# Video_out.net
KiCad netlist of a schematic drawn in Altium Designer
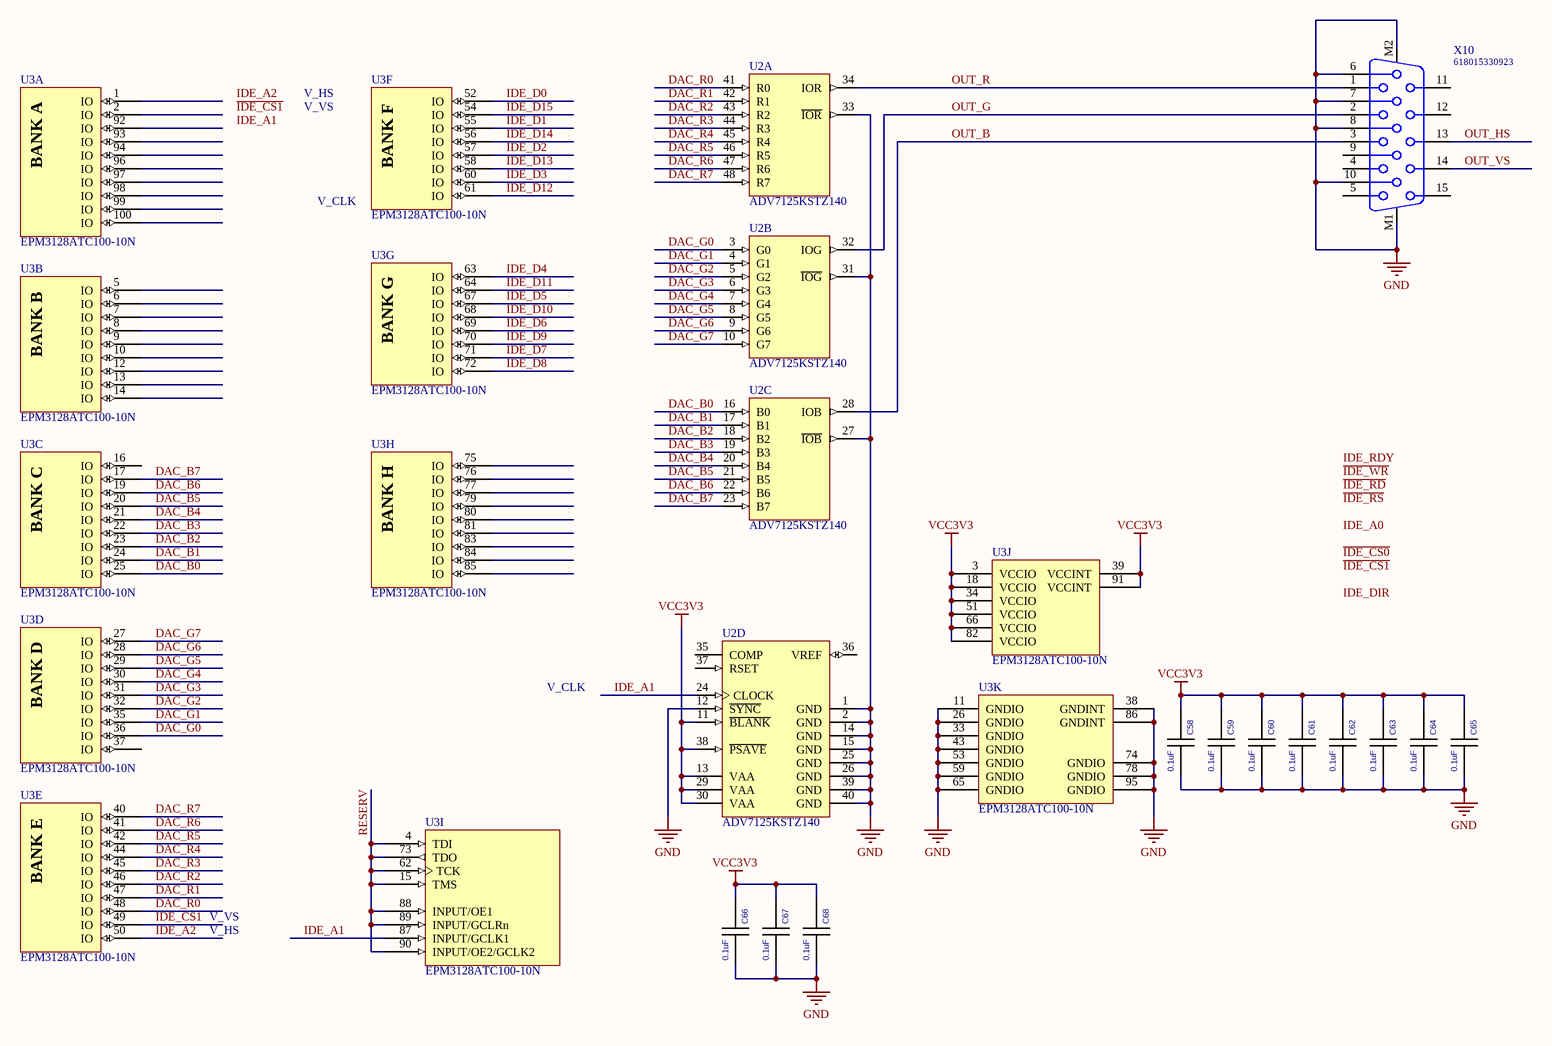
[diagram p0: Video out.SchDoc]

(export (version "E")
  (design (tool "Eeschema 10.0.6"))
  (components
    (comp (ref "C58")
      (value "0.1uF")
      (footprint "C-CHIP")
      (description "CAPCHIP")
      (libsource (lib "*") (part "CAPCHIP"))
    )
    (comp (ref "C59")
      (value "0.1uF")
      (footprint "C-CHIP")
      (description "CAPCHIP")
      (libsource (lib "*") (part "CAPCHIP"))
    )
    (comp (ref "C60")
      (value "0.1uF")
      (footprint "C-CHIP")
      (description "CAPCHIP")
      (libsource (lib "*") (part "CAPCHIP"))
    )
    (comp (ref "C61")
      (value "0.1uF")
      (footprint "C-CHIP")
      (description "CAPCHIP")
      (libsource (lib "*") (part "CAPCHIP"))
    )
    (comp (ref "C62")
      (value "0.1uF")
      (footprint "C-CHIP")
      (description "CAPCHIP")
      (libsource (lib "*") (part "CAPCHIP"))
    )
    (comp (ref "C63")
      (value "0.1uF")
      (footprint "C-CHIP")
      (description "CAPCHIP")
      (libsource (lib "*") (part "CAPCHIP"))
    )
    (comp (ref "C64")
      (value "0.1uF")
      (footprint "C-CHIP")
      (description "CAPCHIP")
      (libsource (lib "*") (part "CAPCHIP"))
    )
    (comp (ref "C65")
      (value "0.1uF")
      (footprint "C-CHIP")
      (description "CAPCHIP")
      (libsource (lib "*") (part "CAPCHIP"))
    )
    (comp (ref "C66")
      (value "0.1uF")
      (footprint "C-CHIP")
      (description "CAPCHIP")
      (libsource (lib "*") (part "CAPCHIP"))
    )
    (comp (ref "C67")
      (value "0.1uF")
      (footprint "C-CHIP")
      (description "CAPCHIP")
      (libsource (lib "*") (part "CAPCHIP"))
    )
    (comp (ref "C68")
      (value "0.1uF")
      (footprint "C-CHIP")
      (description "CAPCHIP")
      (libsource (lib "*") (part "CAPCHIP"))
    )
    (comp (ref "U2")
      (value "ADV7125KSTZ140")
      (footprint "ST-48_N")
      (fields (field (name "GENERIC PART NUMBER") "ADV7125") (field (name "MANUFACTURER") "Analog Devices"))
      (libsource (lib "Altium Content Vault") (part "ADI-ADV7125-ST-48"))
    )
    (comp (ref "U3")
      (value "EPM3128ATC100-10N")
      (footprint "ALTR-TQFP100_A-120_D1-140_L")
      (description "MAX(R) 3000A CPLD, 80 I/Os, Speed Grade 5, Commercial Grade, 100-Pin TQFP, RoHS")
      (fields (field (name "MANUFACTURER") "Altera"))
      (libsource (lib "Altium Content Vault") (part "ALTR-EPM3128A-TQFP-100"))
    )
    (comp (ref "X10")
      (value "618015330923")
      (footprint "618015330923")
      (description "Female High Density PCB Connector with Hex Screw WR-DSUB, Angled, 15 pins")
      (fields (field (name "MANUFACTURER") "Wurth Elektronik") (field (name "PUBLISHER") "WurthElektronik"))
      (libsource (lib "Altium Content Vault") (part "WE-CN-3S-2F-D15"))
    )
  )
  (nets
    (net (code "1") (name "/DAC_B0") (class "Default")
      (node (ref "U2") (pin "16") (pinfunction "B0_16") (pintype "input"))
      (node (ref "U3") (pin "25") (pinfunction "IO_25") (pintype "bidirectional"))
    )
    (net (code "2") (name "/DAC_B1") (class "Default")
      (node (ref "U2") (pin "17") (pinfunction "B1_17") (pintype "input"))
      (node (ref "U3") (pin "24") (pinfunction "IO_24") (pintype "bidirectional"))
    )
    (net (code "3") (name "/DAC_B2") (class "Default")
      (node (ref "U2") (pin "18") (pinfunction "B2_18") (pintype "input"))
      (node (ref "U3") (pin "23") (pinfunction "IO_23") (pintype "bidirectional"))
    )
    (net (code "4") (name "/DAC_B3") (class "Default")
      (node (ref "U2") (pin "19") (pinfunction "B3_19") (pintype "input"))
      (node (ref "U3") (pin "22") (pinfunction "IO_22") (pintype "bidirectional"))
    )
    (net (code "5") (name "/DAC_B4") (class "Default")
      (node (ref "U2") (pin "20") (pinfunction "B4_20") (pintype "input"))
      (node (ref "U3") (pin "21") (pinfunction "IO_21") (pintype "bidirectional"))
    )
    (net (code "6") (name "/DAC_B5") (class "Default")
      (node (ref "U2") (pin "21") (pinfunction "B5_21") (pintype "input"))
      (node (ref "U3") (pin "20") (pinfunction "IO_20") (pintype "bidirectional"))
    )
    (net (code "7") (name "/DAC_B6") (class "Default")
      (node (ref "U2") (pin "22") (pinfunction "B6_22") (pintype "input"))
      (node (ref "U3") (pin "19") (pinfunction "IO_19") (pintype "bidirectional"))
    )
    (net (code "8") (name "/DAC_B7") (class "Default")
      (node (ref "U2") (pin "23") (pinfunction "B7_23") (pintype "input"))
      (node (ref "U3") (pin "17") (pinfunction "IO_17") (pintype "bidirectional"))
    )
    (net (code "9") (name "/DAC_G0") (class "Default")
      (node (ref "U2") (pin "3") (pinfunction "G0_3") (pintype "input"))
      (node (ref "U3") (pin "36") (pinfunction "IO_36") (pintype "bidirectional"))
    )
    (net (code "10") (name "/DAC_G1") (class "Default")
      (node (ref "U2") (pin "4") (pinfunction "G1_4") (pintype "input"))
      (node (ref "U3") (pin "35") (pinfunction "IO_35") (pintype "bidirectional"))
    )
    (net (code "11") (name "/DAC_G2") (class "Default")
      (node (ref "U2") (pin "5") (pinfunction "G2_5") (pintype "input"))
      (node (ref "U3") (pin "32") (pinfunction "IO_32") (pintype "bidirectional"))
    )
    (net (code "12") (name "/DAC_G3") (class "Default")
      (node (ref "U2") (pin "6") (pinfunction "G3_6") (pintype "input"))
      (node (ref "U3") (pin "31") (pinfunction "IO_31") (pintype "bidirectional"))
    )
    (net (code "13") (name "/DAC_G4") (class "Default")
      (node (ref "U2") (pin "7") (pinfunction "G4_7") (pintype "input"))
      (node (ref "U3") (pin "30") (pinfunction "IO_30") (pintype "bidirectional"))
    )
    (net (code "14") (name "/DAC_G5") (class "Default")
      (node (ref "U2") (pin "8") (pinfunction "G5_8") (pintype "input"))
      (node (ref "U3") (pin "29") (pinfunction "IO_29") (pintype "bidirectional"))
    )
    (net (code "15") (name "/DAC_G6") (class "Default")
      (node (ref "U2") (pin "9") (pinfunction "G6_9") (pintype "input"))
      (node (ref "U3") (pin "28") (pinfunction "IO_28") (pintype "bidirectional"))
    )
    (net (code "16") (name "/DAC_G7") (class "Default")
      (node (ref "U2") (pin "10") (pinfunction "G7_10") (pintype "input"))
      (node (ref "U3") (pin "27") (pinfunction "IO_27") (pintype "bidirectional"))
    )
    (net (code "17") (name "/DAC_R0") (class "Default")
      (node (ref "U2") (pin "41") (pinfunction "R0_41") (pintype "input"))
      (node (ref "U3") (pin "48") (pinfunction "IO_48") (pintype "bidirectional"))
    )
    (net (code "18") (name "/DAC_R1") (class "Default")
      (node (ref "U2") (pin "42") (pinfunction "R1_42") (pintype "input"))
      (node (ref "U3") (pin "47") (pinfunction "IO_47") (pintype "bidirectional"))
    )
    (net (code "19") (name "/DAC_R2") (class "Default")
      (node (ref "U2") (pin "43") (pinfunction "R2_43") (pintype "input"))
      (node (ref "U3") (pin "46") (pinfunction "IO_46") (pintype "bidirectional"))
    )
    (net (code "20") (name "/DAC_R3") (class "Default")
      (node (ref "U2") (pin "44") (pinfunction "R3_44") (pintype "input"))
      (node (ref "U3") (pin "45") (pinfunction "IO_45") (pintype "bidirectional"))
    )
    (net (code "21") (name "/DAC_R4") (class "Default")
      (node (ref "U2") (pin "45") (pinfunction "R4_45") (pintype "input"))
      (node (ref "U3") (pin "44") (pinfunction "IO_44") (pintype "bidirectional"))
    )
    (net (code "22") (name "/DAC_R5") (class "Default")
      (node (ref "U2") (pin "46") (pinfunction "R5_46") (pintype "input"))
      (node (ref "U3") (pin "42") (pinfunction "IO_42") (pintype "bidirectional"))
    )
    (net (code "23") (name "/DAC_R6") (class "Default")
      (node (ref "U2") (pin "47") (pinfunction "R6_47") (pintype "input"))
      (node (ref "U3") (pin "41") (pinfunction "IO_41") (pintype "bidirectional"))
    )
    (net (code "24") (name "/DAC_R7") (class "Default")
      (node (ref "U2") (pin "48") (pinfunction "R7_48") (pintype "input"))
      (node (ref "U3") (pin "40") (pinfunction "IO_40") (pintype "bidirectional"))
    )
    (net (code "26") (name "/IDE_A1") (class "Default")
      (node (ref "U2") (pin "24") (pinfunction "CLOCK_24") (pintype "input"))
      (node (ref "U3") (pin "87") (pinfunction "INPUT/GCLK1_87") (pintype "input"))
    )
    (net (code "27") (name "/IDE_A2") (class "Default")
      (node (ref "U3") (pin "50") (pinfunction "IO_50") (pintype "bidirectional"))
    )
    (net (code "28") (name "/IDE_D0") (class "Default")
      (node (ref "U3") (pin "52") (pinfunction "IO_52") (pintype "bidirectional"))
    )
    (net (code "29") (name "/IDE_D1") (class "Default")
      (node (ref "U3") (pin "55") (pinfunction "IO_55") (pintype "bidirectional"))
    )
    (net (code "30") (name "/IDE_D2") (class "Default")
      (node (ref "U3") (pin "57") (pinfunction "IO_57") (pintype "bidirectional"))
    )
    (net (code "31") (name "/IDE_D3") (class "Default")
      (node (ref "U3") (pin "60") (pinfunction "IO_60") (pintype "bidirectional"))
    )
    (net (code "32") (name "/IDE_D4") (class "Default")
      (node (ref "U3") (pin "63") (pinfunction "IO_63") (pintype "bidirectional"))
    )
    (net (code "33") (name "/IDE_D5") (class "Default")
      (node (ref "U3") (pin "67") (pinfunction "IO_67") (pintype "bidirectional"))
    )
    (net (code "34") (name "/IDE_D6") (class "Default")
      (node (ref "U3") (pin "69") (pinfunction "IO_69") (pintype "bidirectional"))
    )
    (net (code "35") (name "/IDE_D7") (class "Default")
      (node (ref "U3") (pin "71") (pinfunction "IO_71") (pintype "bidirectional"))
    )
    (net (code "36") (name "/IDE_D8") (class "Default")
      (node (ref "U3") (pin "72") (pinfunction "IO_72") (pintype "bidirectional"))
    )
    (net (code "37") (name "/IDE_D9") (class "Default")
      (node (ref "U3") (pin "70") (pinfunction "IO_70") (pintype "bidirectional"))
    )
    (net (code "38") (name "/IDE_D10") (class "Default")
      (node (ref "U3") (pin "68") (pinfunction "IO_68") (pintype "bidirectional"))
    )
    (net (code "39") (name "/IDE_D11") (class "Default")
      (node (ref "U3") (pin "64") (pinfunction "IO_64") (pintype "bidirectional"))
    )
    (net (code "40") (name "/IDE_D12") (class "Default")
      (node (ref "U3") (pin "61") (pinfunction "IO_61") (pintype "bidirectional"))
    )
    (net (code "41") (name "/IDE_D13") (class "Default")
      (node (ref "U3") (pin "58") (pinfunction "IO_58") (pintype "bidirectional"))
    )
    (net (code "42") (name "/IDE_D14") (class "Default")
      (node (ref "U3") (pin "56") (pinfunction "IO_56") (pintype "bidirectional"))
    )
    (net (code "43") (name "/IDE_D15") (class "Default")
      (node (ref "U3") (pin "54") (pinfunction "IO_54") (pintype "bidirectional"))
    )
    (net (code "46") (name "/OUT_B") (class "Default")
      (node (ref "U2") (pin "28") (pinfunction "IOB_28") (pintype "output"))
      (node (ref "X10") (pin "3") (pinfunction "3_3") (pintype "passive"))
    )
    (net (code "47") (name "/OUT_G") (class "Default")
      (node (ref "U2") (pin "32") (pinfunction "IOG_32") (pintype "output"))
      (node (ref "X10") (pin "2") (pinfunction "2_2") (pintype "passive"))
    )
    (net (code "48") (name "/OUT_HS") (class "Default")
      (node (ref "X10") (pin "13") (pinfunction "13_13") (pintype "passive"))
    )
    (net (code "49") (name "/OUT_R") (class "Default")
      (node (ref "U2") (pin "34") (pinfunction "IOR_34") (pintype "output"))
      (node (ref "X10") (pin "1") (pinfunction "1_1") (pintype "passive"))
    )
    (net (code "50") (name "/OUT_VS") (class "Default")
      (node (ref "X10") (pin "14") (pinfunction "14_14") (pintype "passive"))
    )
    (net (code "51") (name "/RESERV") (class "Default")
      (node (ref "U3") (pin "15") (pinfunction "TMS_15") (pintype "input"))
      (node (ref "U3") (pin "4") (pinfunction "TDI_4") (pintype "input"))
      (node (ref "U3") (pin "62") (pinfunction "TCK_62") (pintype "input"))
      (node (ref "U3") (pin "73") (pinfunction "TDO_73") (pintype "output"))
      (node (ref "U3") (pin "88") (pinfunction "INPUT/OE1_88") (pintype "input"))
      (node (ref "U3") (pin "89") (pinfunction "INPUT/GCLRn_89") (pintype "input"))
      (node (ref "U3") (pin "90") (pinfunction "INPUT/OE2/GCLK2_90") (pintype "input"))
    )
    (net (code "53") (name "/~{IDE_CS1}") (class "Default")
      (node (ref "U3") (pin "49") (pinfunction "IO_49") (pintype "bidirectional"))
    )
    (net (code "57") (name "GND") (class "Default")
      (node (ref "C58") (pin "2") (pinfunction "2_2") (pintype "passive"))
      (node (ref "C59") (pin "2") (pinfunction "2_2") (pintype "passive"))
      (node (ref "C60") (pin "2") (pinfunction "2_2") (pintype "passive"))
      (node (ref "C61") (pin "2") (pinfunction "2_2") (pintype "passive"))
      (node (ref "C62") (pin "2") (pinfunction "2_2") (pintype "passive"))
      (node (ref "C63") (pin "2") (pinfunction "2_2") (pintype "passive"))
      (node (ref "C64") (pin "2") (pinfunction "2_2") (pintype "passive"))
      (node (ref "C65") (pin "2") (pinfunction "2_2") (pintype "passive"))
      (node (ref "C66") (pin "2") (pinfunction "2_2") (pintype "passive"))
      (node (ref "C67") (pin "2") (pinfunction "2_2") (pintype "passive"))
      (node (ref "C68") (pin "2") (pinfunction "2_2") (pintype "passive"))
      (node (ref "U2") (pin "1") (pinfunction "GND_1") (pintype "power_in"))
      (node (ref "U2") (pin "12") (pinfunction "~{SYNC}_12") (pintype "input"))
      (node (ref "U2") (pin "14") (pinfunction "GND_14") (pintype "power_in"))
      (node (ref "U2") (pin "15") (pinfunction "GND_15") (pintype "power_in"))
      (node (ref "U2") (pin "2") (pinfunction "GND_2") (pintype "power_in"))
      (node (ref "U2") (pin "25") (pinfunction "GND_25") (pintype "power_in"))
      (node (ref "U2") (pin "26") (pinfunction "GND_26") (pintype "power_in"))
      (node (ref "U2") (pin "27") (pinfunction "~{IOB}_27") (pintype "output"))
      (node (ref "U2") (pin "31") (pinfunction "~{IOG}_31") (pintype "output"))
      (node (ref "U2") (pin "33") (pinfunction "~{IOR}_33") (pintype "output"))
      (node (ref "U2") (pin "39") (pinfunction "GND_39") (pintype "power_in"))
      (node (ref "U2") (pin "40") (pinfunction "GND_40") (pintype "power_in"))
      (node (ref "U3") (pin "11") (pinfunction "GNDIO_11") (pintype "power_in"))
      (node (ref "U3") (pin "26") (pinfunction "GNDIO_26") (pintype "power_in"))
      (node (ref "U3") (pin "33") (pinfunction "GNDIO_33") (pintype "power_in"))
      (node (ref "U3") (pin "38") (pinfunction "GNDINT_38") (pintype "power_in"))
      (node (ref "U3") (pin "43") (pinfunction "GNDIO_43") (pintype "power_in"))
      (node (ref "U3") (pin "53") (pinfunction "GNDIO_53") (pintype "power_in"))
      (node (ref "U3") (pin "59") (pinfunction "GNDIO_59") (pintype "power_in"))
      (node (ref "U3") (pin "65") (pinfunction "GNDIO_65") (pintype "power_in"))
      (node (ref "U3") (pin "74") (pinfunction "GNDIO_74") (pintype "power_in"))
      (node (ref "U3") (pin "78") (pinfunction "GNDIO_78") (pintype "power_in"))
      (node (ref "U3") (pin "86") (pinfunction "GNDINT_86") (pintype "power_in"))
      (node (ref "U3") (pin "95") (pinfunction "GNDIO_95") (pintype "power_in"))
      (node (ref "X10") (pin "10") (pinfunction "10_10") (pintype "passive"))
      (node (ref "X10") (pin "6") (pinfunction "6_6") (pintype "passive"))
      (node (ref "X10") (pin "7") (pinfunction "7_7") (pintype "passive"))
      (node (ref "X10") (pin "8") (pinfunction "8_8") (pintype "passive"))
      (node (ref "X10") (pin "M1") (pinfunction "M1_M1") (pintype "passive"))
      (node (ref "X10") (pin "M2") (pinfunction "M2_M2") (pintype "passive"))
    )
    (net (code "58") (name "VCC3V3") (class "Default")
      (node (ref "C58") (pin "1") (pinfunction "1_1") (pintype "passive"))
      (node (ref "C59") (pin "1") (pinfunction "1_1") (pintype "passive"))
      (node (ref "C60") (pin "1") (pinfunction "1_1") (pintype "passive"))
      (node (ref "C61") (pin "1") (pinfunction "1_1") (pintype "passive"))
      (node (ref "C62") (pin "1") (pinfunction "1_1") (pintype "passive"))
      (node (ref "C63") (pin "1") (pinfunction "1_1") (pintype "passive"))
      (node (ref "C64") (pin "1") (pinfunction "1_1") (pintype "passive"))
      (node (ref "C65") (pin "1") (pinfunction "1_1") (pintype "passive"))
      (node (ref "C66") (pin "1") (pinfunction "1_1") (pintype "passive"))
      (node (ref "C67") (pin "1") (pinfunction "1_1") (pintype "passive"))
      (node (ref "C68") (pin "1") (pinfunction "1_1") (pintype "passive"))
      (node (ref "U2") (pin "11") (pinfunction "~{BLANK}_11") (pintype "input"))
      (node (ref "U2") (pin "13") (pinfunction "VAA_13") (pintype "power_in"))
      (node (ref "U2") (pin "29") (pinfunction "VAA_29") (pintype "power_in"))
      (node (ref "U2") (pin "30") (pinfunction "VAA_30") (pintype "power_in"))
      (node (ref "U2") (pin "38") (pinfunction "~{PSAVE}_38") (pintype "input"))
      (node (ref "U3") (pin "18") (pinfunction "VCCIO_18") (pintype "power_in"))
      (node (ref "U3") (pin "3") (pinfunction "VCCIO_3") (pintype "power_in"))
      (node (ref "U3") (pin "34") (pinfunction "VCCIO_34") (pintype "power_in"))
      (node (ref "U3") (pin "39") (pinfunction "VCCINT_39") (pintype "power_in"))
      (node (ref "U3") (pin "51") (pinfunction "VCCIO_51") (pintype "power_in"))
      (node (ref "U3") (pin "66") (pinfunction "VCCIO_66") (pintype "power_in"))
      (node (ref "U3") (pin "82") (pinfunction "VCCIO_82") (pintype "power_in"))
      (node (ref "U3") (pin "91") (pinfunction "VCCINT_91") (pintype "power_in"))
    )
    (net (code "59") (name "unconnected-(U2D-COMP-Pad35)") (class "Default")
      (node (ref "U2") (pin "35") (pinfunction "COMP_35") (pintype "passive"))
    )
    (net (code "60") (name "unconnected-(U2D-RSET-Pad37)") (class "Default")
      (node (ref "U2") (pin "37") (pinfunction "RSET_37") (pintype "input"))
    )
    (net (code "61") (name "unconnected-(U2D-VREF-Pad36)") (class "Default")
      (node (ref "U2") (pin "36") (pinfunction "VREF_36") (pintype "bidirectional"))
    )
    (net (code "62") (name "unconnected-(U3A-IO-Pad1)") (class "Default")
      (node (ref "U3") (pin "1") (pinfunction "IO_1") (pintype "bidirectional"))
    )
    (net (code "63") (name "unconnected-(U3A-IO-Pad2)") (class "Default")
      (node (ref "U3") (pin "2") (pinfunction "IO_2") (pintype "bidirectional"))
    )
    (net (code "64") (name "unconnected-(U3A-IO-Pad92)") (class "Default")
      (node (ref "U3") (pin "92") (pinfunction "IO_92") (pintype "bidirectional"))
    )
    (net (code "65") (name "unconnected-(U3A-IO-Pad93)") (class "Default")
      (node (ref "U3") (pin "93") (pinfunction "IO_93") (pintype "bidirectional"))
    )
    (net (code "66") (name "unconnected-(U3A-IO-Pad94)") (class "Default")
      (node (ref "U3") (pin "94") (pinfunction "IO_94") (pintype "bidirectional"))
    )
    (net (code "67") (name "unconnected-(U3A-IO-Pad96)") (class "Default")
      (node (ref "U3") (pin "96") (pinfunction "IO_96") (pintype "bidirectional"))
    )
    (net (code "68") (name "unconnected-(U3A-IO-Pad97)") (class "Default")
      (node (ref "U3") (pin "97") (pinfunction "IO_97") (pintype "bidirectional"))
    )
    (net (code "69") (name "unconnected-(U3A-IO-Pad98)") (class "Default")
      (node (ref "U3") (pin "98") (pinfunction "IO_98") (pintype "bidirectional"))
    )
    (net (code "70") (name "unconnected-(U3A-IO-Pad99)") (class "Default")
      (node (ref "U3") (pin "99") (pinfunction "IO_99") (pintype "bidirectional"))
    )
    (net (code "71") (name "unconnected-(U3A-IO-Pad100)") (class "Default")
      (node (ref "U3") (pin "100") (pinfunction "IO_100") (pintype "bidirectional"))
    )
    (net (code "72") (name "unconnected-(U3B-IO-Pad5)") (class "Default")
      (node (ref "U3") (pin "5") (pinfunction "IO_5") (pintype "bidirectional"))
    )
    (net (code "73") (name "unconnected-(U3B-IO-Pad6)") (class "Default")
      (node (ref "U3") (pin "6") (pinfunction "IO_6") (pintype "bidirectional"))
    )
    (net (code "74") (name "unconnected-(U3B-IO-Pad7)") (class "Default")
      (node (ref "U3") (pin "7") (pinfunction "IO_7") (pintype "bidirectional"))
    )
    (net (code "75") (name "unconnected-(U3B-IO-Pad8)") (class "Default")
      (node (ref "U3") (pin "8") (pinfunction "IO_8") (pintype "bidirectional"))
    )
    (net (code "76") (name "unconnected-(U3B-IO-Pad9)") (class "Default")
      (node (ref "U3") (pin "9") (pinfunction "IO_9") (pintype "bidirectional"))
    )
    (net (code "77") (name "unconnected-(U3B-IO-Pad10)") (class "Default")
      (node (ref "U3") (pin "10") (pinfunction "IO_10") (pintype "bidirectional"))
    )
    (net (code "78") (name "unconnected-(U3B-IO-Pad12)") (class "Default")
      (node (ref "U3") (pin "12") (pinfunction "IO_12") (pintype "bidirectional"))
    )
    (net (code "79") (name "unconnected-(U3B-IO-Pad13)") (class "Default")
      (node (ref "U3") (pin "13") (pinfunction "IO_13") (pintype "bidirectional"))
    )
    (net (code "80") (name "unconnected-(U3B-IO-Pad14)") (class "Default")
      (node (ref "U3") (pin "14") (pinfunction "IO_14") (pintype "bidirectional"))
    )
    (net (code "81") (name "unconnected-(U3C-IO-Pad16)") (class "Default")
      (node (ref "U3") (pin "16") (pinfunction "IO_16") (pintype "bidirectional"))
    )
    (net (code "82") (name "unconnected-(U3D-IO-Pad37)") (class "Default")
      (node (ref "U3") (pin "37") (pinfunction "IO_37") (pintype "bidirectional"))
    )
    (net (code "83") (name "unconnected-(U3H-IO-Pad75)") (class "Default")
      (node (ref "U3") (pin "75") (pinfunction "IO_75") (pintype "bidirectional"))
    )
    (net (code "84") (name "unconnected-(U3H-IO-Pad76)") (class "Default")
      (node (ref "U3") (pin "76") (pinfunction "IO_76") (pintype "bidirectional"))
    )
    (net (code "85") (name "unconnected-(U3H-IO-Pad77)") (class "Default")
      (node (ref "U3") (pin "77") (pinfunction "IO_77") (pintype "bidirectional"))
    )
    (net (code "86") (name "unconnected-(U3H-IO-Pad79)") (class "Default")
      (node (ref "U3") (pin "79") (pinfunction "IO_79") (pintype "bidirectional"))
    )
    (net (code "87") (name "unconnected-(U3H-IO-Pad80)") (class "Default")
      (node (ref "U3") (pin "80") (pinfunction "IO_80") (pintype "bidirectional"))
    )
    (net (code "88") (name "unconnected-(U3H-IO-Pad81)") (class "Default")
      (node (ref "U3") (pin "81") (pinfunction "IO_81") (pintype "bidirectional"))
    )
    (net (code "89") (name "unconnected-(U3H-IO-Pad83)") (class "Default")
      (node (ref "U3") (pin "83") (pinfunction "IO_83") (pintype "bidirectional"))
    )
    (net (code "90") (name "unconnected-(U3H-IO-Pad84)") (class "Default")
      (node (ref "U3") (pin "84") (pinfunction "IO_84") (pintype "bidirectional"))
    )
    (net (code "91") (name "unconnected-(U3H-IO-Pad85)") (class "Default")
      (node (ref "U3") (pin "85") (pinfunction "IO_85") (pintype "bidirectional"))
    )
    (net (code "92") (name "unconnected-(X10-Pad4)") (class "Default")
      (node (ref "X10") (pin "4") (pinfunction "4_4") (pintype "passive"))
    )
    (net (code "93") (name "unconnected-(X10-Pad5)") (class "Default")
      (node (ref "X10") (pin "5") (pinfunction "5_5") (pintype "passive"))
    )
    (net (code "94") (name "unconnected-(X10-Pad9)") (class "Default")
      (node (ref "X10") (pin "9") (pinfunction "9_9") (pintype "passive"))
    )
    (net (code "95") (name "unconnected-(X10-Pad11)") (class "Default")
      (node (ref "X10") (pin "11") (pinfunction "11_11") (pintype "passive"))
    )
    (net (code "96") (name "unconnected-(X10-Pad12)") (class "Default")
      (node (ref "X10") (pin "12") (pinfunction "12_12") (pintype "passive"))
    )
    (net (code "97") (name "unconnected-(X10-Pad15)") (class "Default")
      (node (ref "X10") (pin "15") (pinfunction "15_15") (pintype "passive"))
    )
  )
)
